# Bikota.net
KiCad netlist of a schematic drawn in EAGLE
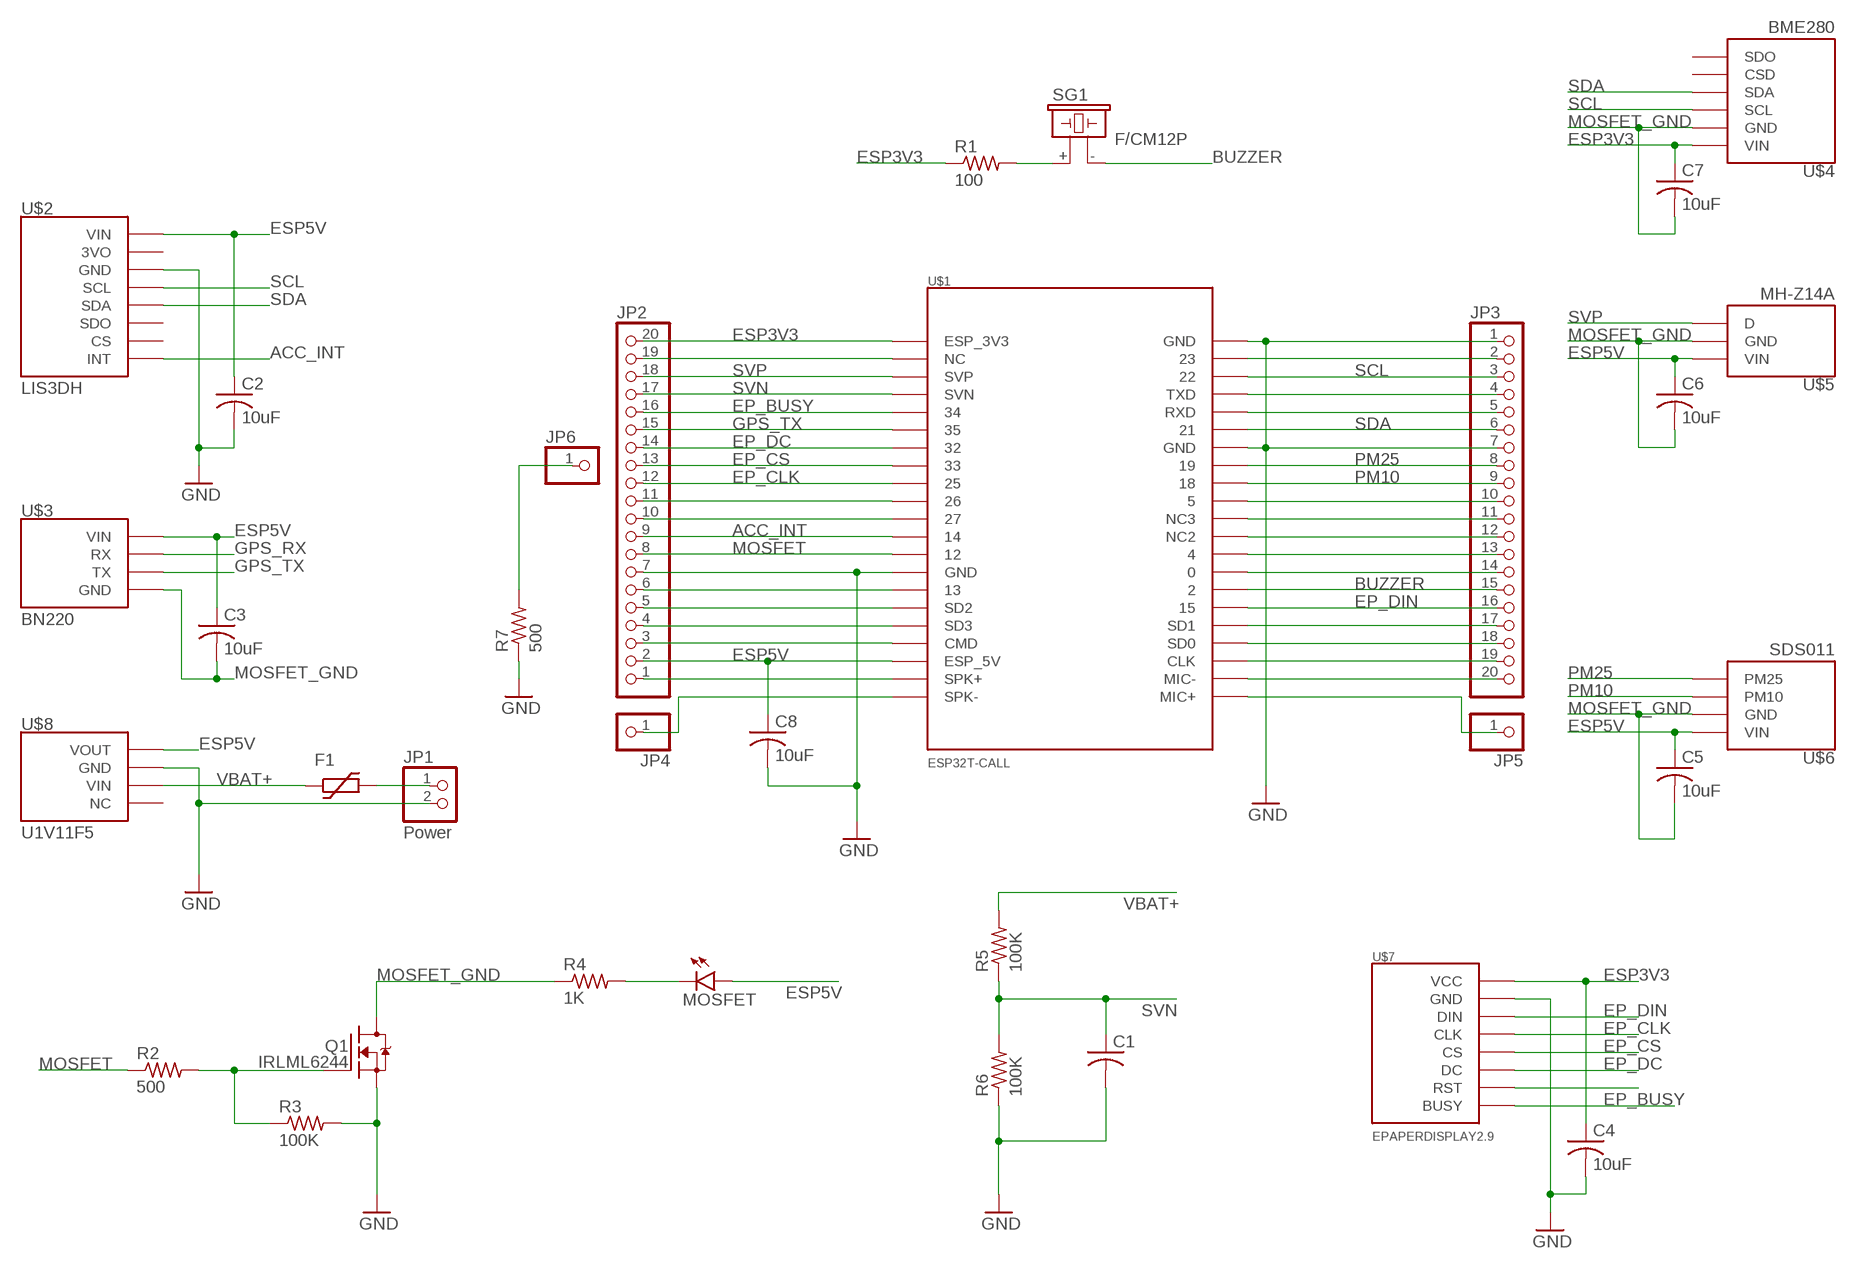
[diagram p0: schematic, sheet 1]

(export (version "E")
  (design (tool "Eeschema 10.0.6"))
  (components
    (comp (ref "C1")
      (value "C-USC0805")
      (footprint "eagle-import:C0805")
      (libsource (lib "eagle-import") (part "C-USC0805"))
    )
    (comp (ref "C2")
      (value "10uF")
      (footprint "eagle-import:C0805")
      (libsource (lib "eagle-import") (part "C-USC0805"))
    )
    (comp (ref "C3")
      (value "10uF")
      (footprint "eagle-import:C0805")
      (libsource (lib "eagle-import") (part "C-USC0805"))
    )
    (comp (ref "C4")
      (value "10uF")
      (footprint "eagle-import:C0805")
      (libsource (lib "eagle-import") (part "C-USC0805"))
    )
    (comp (ref "C5")
      (value "10uF")
      (footprint "eagle-import:C0805")
      (libsource (lib "eagle-import") (part "C-USC0805"))
    )
    (comp (ref "C6")
      (value "10uF")
      (footprint "eagle-import:C0805")
      (libsource (lib "eagle-import") (part "C-USC0805"))
    )
    (comp (ref "C7")
      (value "10uF")
      (footprint "eagle-import:C0805")
      (libsource (lib "eagle-import") (part "C-USC0805"))
    )
    (comp (ref "C8")
      (value "10uF")
      (footprint "eagle-import:C0805")
      (libsource (lib "eagle-import") (part "C-USC0805"))
    )
    (comp (ref "F1")
      (value "1206L")
      (footprint "eagle-import:1206L")
      (libsource (lib "eagle-import") (part "1206L"))
    )
    (comp (ref "JP1")
      (value "Power")
      (footprint "eagle-import:1X02")
      (libsource (lib "eagle-import") (part "PINHD-1X2"))
    )
    (comp (ref "JP2")
      (value "PINHD-1X20")
      (footprint "eagle-import:1X20")
      (libsource (lib "eagle-import") (part "PINHD-1X20"))
    )
    (comp (ref "JP3")
      (value "PINHD-1X20")
      (footprint "eagle-import:1X20")
      (libsource (lib "eagle-import") (part "PINHD-1X20"))
    )
    (comp (ref "JP4")
      (value "PINHD-1X1")
      (footprint "eagle-import:1X01")
      (libsource (lib "eagle-import") (part "PINHD-1X1"))
    )
    (comp (ref "JP5")
      (value "PINHD-1X1")
      (footprint "eagle-import:1X01")
      (libsource (lib "eagle-import") (part "PINHD-1X1"))
    )
    (comp (ref "JP6")
      (value "PINHD-1X1")
      (footprint "eagle-import:1X01")
      (libsource (lib "eagle-import") (part "PINHD-1X1"))
    )
    (comp (ref "MOSFET")
      (value "LEDCHIPLED_0805")
      (footprint "eagle-import:CHIPLED_0805")
      (libsource (lib "eagle-import") (part "LEDCHIPLED_0805"))
    )
    (comp (ref "Q1")
      (value "IRLML6244")
      (footprint "eagle-import:SOT23")
      (fields (field (name "MF") "Internat. Rectifier") (field (name "MPN") "IRLML6244TRPbF"))
      (libsource (lib "eagle-import") (part "IRLML6244"))
    )
    (comp (ref "R1")
      (value "100")
      (footprint "eagle-import:R0805")
      (libsource (lib "eagle-import") (part "R-US_R0805"))
    )
    (comp (ref "R2")
      (value "500")
      (footprint "eagle-import:R0805")
      (libsource (lib "eagle-import") (part "R-US_R0805"))
    )
    (comp (ref "R3")
      (value "100K")
      (footprint "eagle-import:R0805")
      (libsource (lib "eagle-import") (part "R-US_R0805"))
    )
    (comp (ref "R4")
      (value "1K")
      (footprint "eagle-import:R0805")
      (libsource (lib "eagle-import") (part "R-US_R0805"))
    )
    (comp (ref "R5")
      (value "100K")
      (footprint "eagle-import:R0805")
      (libsource (lib "eagle-import") (part "R-US_R0805"))
    )
    (comp (ref "R6")
      (value "100K")
      (footprint "eagle-import:R0805")
      (libsource (lib "eagle-import") (part "R-US_R0805"))
    )
    (comp (ref "R7")
      (value "500")
      (footprint "eagle-import:R0805")
      (libsource (lib "eagle-import") (part "R-US_R0805"))
    )
    (comp (ref "SG1")
      (value "F/CM12P")
      (footprint "eagle-import:F_CM12P")
      (libsource (lib "eagle-import") (part "F/CM12P"))
    )
    (comp (ref "U$1")
      (value "ESP32T-CALL")
      (footprint "eagle-import:ESP32T-CALL")
      (libsource (lib "eagle-import") (part "ESP32T-CALL"))
    )
    (comp (ref "U$2")
      (value "LIS3DH")
      (footprint "eagle-import:LIS3DH")
      (libsource (lib "eagle-import") (part "LIS3DH"))
    )
    (comp (ref "U$3")
      (value "BN220")
      (footprint "eagle-import:BN220")
      (libsource (lib "eagle-import") (part "BN220"))
    )
    (comp (ref "U$4")
      (value "BME280")
      (footprint "eagle-import:BME280")
      (libsource (lib "eagle-import") (part "BME280"))
    )
    (comp (ref "U$5")
      (value "MH-Z14A")
      (footprint "eagle-import:MH-Z14A")
      (libsource (lib "eagle-import") (part "MH-Z14A"))
    )
    (comp (ref "U$6")
      (value "SDS011")
      (footprint "eagle-import:SDS011")
      (libsource (lib "eagle-import") (part "SDS011"))
    )
    (comp (ref "U$7")
      (value "EPAPERDISPLAY2.9")
      (footprint "eagle-import:EPAPERDISPLAY2.9")
      (libsource (lib "eagle-import") (part "EPAPERDISPLAY2.9"))
    )
    (comp (ref "U$8")
      (value "U1V11F5")
      (footprint "eagle-import:U1V11F5")
      (libsource (lib "eagle-import") (part "U1V11F5"))
    )
  )
  (nets
    (net (code "1") (name "/3VO") (class "Default")
      (node (ref "U$2") (pin "P$2") (pinfunction "3VO_P$2") (pintype "power_in"))
    )
    (net (code "2") (name "/ACC_INT") (class "Default")
      (node (ref "JP2") (pin "9") (pinfunction "9_9") (pintype "passive"))
      (node (ref "U$1") (pin "GPIO14") (pinfunction "14_GPIO14") (pintype "bidirectional"))
      (node (ref "U$2") (pin "P$8") (pinfunction "INT_P$8") (pintype "bidirectional"))
    )
    (net (code "3") (name "/BUZZER") (class "Default")
      (node (ref "JP3") (pin "15") (pinfunction "15_15") (pintype "passive"))
      (node (ref "SG1") (pin "-") (pinfunction "2_-") (pintype "passive"))
      (node (ref "U$1") (pin "GPIO2") (pinfunction "2_GPIO2") (pintype "bidirectional"))
    )
    (net (code "4") (name "/EP_BUSY") (class "Default")
      (node (ref "JP2") (pin "16") (pinfunction "16_16") (pintype "passive"))
      (node (ref "U$1") (pin "GPIO34") (pinfunction "34_GPIO34") (pintype "bidirectional"))
      (node (ref "U$7") (pin "P$8") (pinfunction "BUSY_P$8") (pintype "bidirectional"))
    )
    (net (code "5") (name "/EP_CLK") (class "Default")
      (node (ref "JP2") (pin "12") (pinfunction "12_12") (pintype "passive"))
      (node (ref "U$1") (pin "GPIO25") (pinfunction "25_GPIO25") (pintype "bidirectional"))
      (node (ref "U$7") (pin "P$4") (pinfunction "CLK_P$4") (pintype "bidirectional"))
    )
    (net (code "6") (name "/EP_CS") (class "Default")
      (node (ref "JP2") (pin "13") (pinfunction "13_13") (pintype "passive"))
      (node (ref "U$1") (pin "GPIO33") (pinfunction "33_GPIO33") (pintype "bidirectional"))
      (node (ref "U$7") (pin "P$5") (pinfunction "CS_P$5") (pintype "bidirectional"))
    )
    (net (code "7") (name "/EP_DC") (class "Default")
      (node (ref "JP2") (pin "14") (pinfunction "14_14") (pintype "passive"))
      (node (ref "U$1") (pin "GPIO32") (pinfunction "32_GPIO32") (pintype "bidirectional"))
      (node (ref "U$7") (pin "P$6") (pinfunction "DC_P$6") (pintype "bidirectional"))
    )
    (net (code "8") (name "/EP_DIN") (class "Default")
      (node (ref "JP3") (pin "16") (pinfunction "16_16") (pintype "passive"))
      (node (ref "U$1") (pin "GPIO15") (pinfunction "15_GPIO15") (pintype "bidirectional"))
      (node (ref "U$7") (pin "P$3") (pinfunction "DIN_P$3") (pintype "bidirectional"))
    )
    (net (code "9") (name "/ESP3V3") (class "Default")
      (node (ref "C4") (pin "1") (pinfunction "1_1") (pintype "passive"))
      (node (ref "C7") (pin "1") (pinfunction "1_1") (pintype "passive"))
      (node (ref "JP2") (pin "20") (pinfunction "20_20") (pintype "passive"))
      (node (ref "R1") (pin "1") (pinfunction "1_1") (pintype "passive"))
      (node (ref "U$1") (pin "ESP32_3V3") (pinfunction "ESP_3V3_ESP32_3V3") (pintype "power_in"))
      (node (ref "U$4") (pin "P$1") (pinfunction "VIN_P$1") (pintype "power_in"))
      (node (ref "U$7") (pin "P$1") (pinfunction "VCC_P$1") (pintype "power_in"))
    )
    (net (code "10") (name "/ESP5V") (class "Default")
      (node (ref "C2") (pin "1") (pinfunction "1_1") (pintype "passive"))
      (node (ref "C3") (pin "1") (pinfunction "1_1") (pintype "passive"))
      (node (ref "C5") (pin "1") (pinfunction "1_1") (pintype "passive"))
      (node (ref "C6") (pin "1") (pinfunction "1_1") (pintype "passive"))
      (node (ref "C8") (pin "1") (pinfunction "1_1") (pintype "passive"))
      (node (ref "JP2") (pin "2") (pinfunction "2_2") (pintype "passive"))
      (node (ref "MOSFET") (pin "A") (pinfunction "A_A") (pintype "passive"))
      (node (ref "U$1") (pin "ESP32_5V") (pinfunction "ESP_5V_ESP32_5V") (pintype "power_in"))
      (node (ref "U$2") (pin "P$1") (pinfunction "VIN_P$1") (pintype "power_in"))
      (node (ref "U$3") (pin "P$1") (pinfunction "VIN_P$1") (pintype "power_in"))
      (node (ref "U$5") (pin "P$1") (pinfunction "VIN_P$1") (pintype "power_in"))
      (node (ref "U$6") (pin "P$1") (pinfunction "VIN_P$1") (pintype "power_in"))
      (node (ref "U$8") (pin "P$1") (pinfunction "VOUT_P$1") (pintype "power_in"))
    )
    (net (code "11") (name "/GPS_RX") (class "Default")
      (node (ref "U$3") (pin "P$2") (pinfunction "RX_P$2") (pintype "bidirectional"))
    )
    (net (code "12") (name "/GPS_TX") (class "Default")
      (node (ref "JP2") (pin "15") (pinfunction "15_15") (pintype "passive"))
      (node (ref "U$1") (pin "GPIO35") (pinfunction "35_GPIO35") (pintype "bidirectional"))
      (node (ref "U$3") (pin "P$3") (pinfunction "TX_P$3") (pintype "bidirectional"))
    )
    (net (code "13") (name "/MOSFET") (class "Default")
      (node (ref "JP2") (pin "8") (pinfunction "8_8") (pintype "passive"))
      (node (ref "R2") (pin "1") (pinfunction "1_1") (pintype "passive"))
      (node (ref "U$1") (pin "GPIO12") (pinfunction "12_GPIO12") (pintype "bidirectional"))
    )
    (net (code "14") (name "/MOSFET_GND") (class "Default")
      (node (ref "C3") (pin "2") (pinfunction "2_2") (pintype "passive"))
      (node (ref "C5") (pin "2") (pinfunction "2_2") (pintype "passive"))
      (node (ref "C6") (pin "2") (pinfunction "2_2") (pintype "passive"))
      (node (ref "C7") (pin "2") (pinfunction "2_2") (pintype "passive"))
      (node (ref "Q1") (pin "3") (pinfunction "D_3") (pintype "passive"))
      (node (ref "R4") (pin "1") (pinfunction "1_1") (pintype "passive"))
      (node (ref "U$3") (pin "P$4") (pinfunction "GND_P$4") (pintype "power_in"))
      (node (ref "U$4") (pin "P$2") (pinfunction "GND_P$2") (pintype "power_in"))
      (node (ref "U$5") (pin "P$2") (pinfunction "GND_P$2") (pintype "power_in"))
      (node (ref "U$6") (pin "P$2") (pinfunction "GND_P$2") (pintype "power_in"))
    )
    (net (code "15") (name "/PM10") (class "Default")
      (node (ref "JP3") (pin "9") (pinfunction "9_9") (pintype "passive"))
      (node (ref "U$1") (pin "GPIO18") (pinfunction "18_GPIO18") (pintype "bidirectional"))
      (node (ref "U$6") (pin "P$3") (pinfunction "PM10_P$3") (pintype "bidirectional"))
    )
    (net (code "16") (name "/PM25") (class "Default")
      (node (ref "JP3") (pin "8") (pinfunction "8_8") (pintype "passive"))
      (node (ref "U$1") (pin "GPIO19") (pinfunction "19_GPIO19") (pintype "bidirectional"))
      (node (ref "U$6") (pin "P$4") (pinfunction "PM25_P$4") (pintype "bidirectional"))
    )
    (net (code "17") (name "/SCL") (class "Default")
      (node (ref "JP3") (pin "3") (pinfunction "3_3") (pintype "passive"))
      (node (ref "U$1") (pin "GPIO22") (pinfunction "22_GPIO22") (pintype "bidirectional"))
      (node (ref "U$2") (pin "P$4") (pinfunction "SCL_P$4") (pintype "bidirectional"))
      (node (ref "U$4") (pin "P$3") (pinfunction "SCL_P$3") (pintype "bidirectional"))
    )
    (net (code "18") (name "/SDA") (class "Default")
      (node (ref "JP3") (pin "6") (pinfunction "6_6") (pintype "passive"))
      (node (ref "U$1") (pin "GPIO21") (pinfunction "21_GPIO21") (pintype "bidirectional"))
      (node (ref "U$2") (pin "P$5") (pinfunction "SDA_P$5") (pintype "bidirectional"))
      (node (ref "U$4") (pin "P$4") (pinfunction "SDA_P$4") (pintype "bidirectional"))
    )
    (net (code "19") (name "/SVN") (class "Default")
      (node (ref "C1") (pin "1") (pinfunction "1_1") (pintype "passive"))
      (node (ref "JP2") (pin "17") (pinfunction "17_17") (pintype "passive"))
      (node (ref "R5") (pin "1") (pinfunction "1_1") (pintype "passive"))
      (node (ref "R6") (pin "2") (pinfunction "2_2") (pintype "passive"))
      (node (ref "U$1") (pin "SVN") (pinfunction "SVN_SVN") (pintype "bidirectional"))
    )
    (net (code "20") (name "/SVP") (class "Default")
      (node (ref "JP2") (pin "18") (pinfunction "18_18") (pintype "passive"))
      (node (ref "U$1") (pin "SVP") (pinfunction "SVP_SVP") (pintype "bidirectional"))
      (node (ref "U$5") (pin "P$3") (pinfunction "D_P$3") (pintype "bidirectional"))
    )
    (net (code "21") (name "/VBAT+") (class "Default")
      (node (ref "F1") (pin "P$1") (pinfunction "1_P$1") (pintype "passive"))
      (node (ref "R5") (pin "2") (pinfunction "2_2") (pintype "passive"))
      (node (ref "U$8") (pin "P$3") (pinfunction "VIN_P$3") (pintype "power_in"))
    )
    (net (code "22") (name "GND") (class "Default")
      (node (ref "C1") (pin "2") (pinfunction "2_2") (pintype "passive"))
      (node (ref "C2") (pin "2") (pinfunction "2_2") (pintype "passive"))
      (node (ref "C4") (pin "2") (pinfunction "2_2") (pintype "passive"))
      (node (ref "C8") (pin "2") (pinfunction "2_2") (pintype "passive"))
      (node (ref "JP1") (pin "2") (pinfunction "2_2") (pintype "passive"))
      (node (ref "JP2") (pin "7") (pinfunction "7_7") (pintype "passive"))
      (node (ref "JP3") (pin "1") (pinfunction "1_1") (pintype "passive"))
      (node (ref "JP3") (pin "7") (pinfunction "7_7") (pintype "passive"))
      (node (ref "Q1") (pin "2") (pinfunction "S_2") (pintype "passive"))
      (node (ref "R3") (pin "2") (pinfunction "2_2") (pintype "passive"))
      (node (ref "R6") (pin "1") (pinfunction "1_1") (pintype "passive"))
      (node (ref "R7") (pin "1") (pinfunction "1_1") (pintype "passive"))
      (node (ref "U$1") (pin "GND") (pinfunction "GND_GND") (pintype "power_in"))
      (node (ref "U$1") (pin "GND2") (pinfunction "GND_GND2") (pintype "power_in"))
      (node (ref "U$1") (pin "GND3") (pinfunction "GND_GND3") (pintype "power_in"))
      (node (ref "U$2") (pin "P$3") (pinfunction "GND_P$3") (pintype "power_in"))
      (node (ref "U$7") (pin "P$2") (pinfunction "GND_P$2") (pintype "power_in"))
      (node (ref "U$8") (pin "P$2") (pinfunction "GND_P$2") (pintype "power_in"))
    )
    (net (code "23") (name "Net-(F1-2)") (class "Default")
      (node (ref "F1") (pin "P$2") (pinfunction "2_P$2") (pintype "passive"))
      (node (ref "JP1") (pin "1") (pinfunction "1_1") (pintype "passive"))
    )
    (net (code "24") (name "Net-(JP2-Pad1)") (class "Default")
      (node (ref "JP2") (pin "1") (pinfunction "1_1") (pintype "passive"))
      (node (ref "U$1") (pin "SPK+") (pinfunction "SPK+_SPK+") (pintype "bidirectional"))
    )
    (net (code "25") (name "Net-(JP2-Pad3)") (class "Default")
      (node (ref "JP2") (pin "3") (pinfunction "3_3") (pintype "passive"))
      (node (ref "U$1") (pin "CMD") (pinfunction "CMD_CMD") (pintype "bidirectional"))
    )
    (net (code "26") (name "Net-(JP2-Pad4)") (class "Default")
      (node (ref "JP2") (pin "4") (pinfunction "4_4") (pintype "passive"))
      (node (ref "U$1") (pin "SD3") (pinfunction "SD3_SD3") (pintype "bidirectional"))
    )
    (net (code "27") (name "Net-(JP2-Pad5)") (class "Default")
      (node (ref "JP2") (pin "5") (pinfunction "5_5") (pintype "passive"))
      (node (ref "U$1") (pin "SD2") (pinfunction "SD2_SD2") (pintype "bidirectional"))
    )
    (net (code "28") (name "Net-(JP3-Pad4)") (class "Default")
      (node (ref "JP3") (pin "4") (pinfunction "4_4") (pintype "passive"))
      (node (ref "U$1") (pin "TXD") (pinfunction "TXD_TXD") (pintype "bidirectional"))
    )
    (net (code "29") (name "Net-(JP3-Pad5)") (class "Default")
      (node (ref "JP3") (pin "5") (pinfunction "5_5") (pintype "passive"))
      (node (ref "U$1") (pin "RXD") (pinfunction "RXD_RXD") (pintype "bidirectional"))
    )
    (net (code "30") (name "Net-(JP3-Pad11)") (class "Default")
      (node (ref "JP3") (pin "11") (pinfunction "11_11") (pintype "passive"))
      (node (ref "U$1") (pin "NC3") (pinfunction "NC3_NC3") (pintype "bidirectional"))
    )
    (net (code "31") (name "Net-(JP3-Pad12)") (class "Default")
      (node (ref "JP3") (pin "12") (pinfunction "12_12") (pintype "passive"))
      (node (ref "U$1") (pin "NC2") (pinfunction "NC2_NC2") (pintype "bidirectional"))
    )
    (net (code "32") (name "Net-(JP3-Pad17)") (class "Default")
      (node (ref "JP3") (pin "17") (pinfunction "17_17") (pintype "passive"))
      (node (ref "U$1") (pin "SD1") (pinfunction "SD1_SD1") (pintype "bidirectional"))
    )
    (net (code "33") (name "Net-(JP3-Pad18)") (class "Default")
      (node (ref "JP3") (pin "18") (pinfunction "18_18") (pintype "passive"))
      (node (ref "U$1") (pin "SD0") (pinfunction "SD0_SD0") (pintype "bidirectional"))
    )
    (net (code "34") (name "Net-(JP3-Pad19)") (class "Default")
      (node (ref "JP3") (pin "19") (pinfunction "19_19") (pintype "passive"))
      (node (ref "U$1") (pin "CLK") (pinfunction "CLK_CLK") (pintype "bidirectional"))
    )
    (net (code "35") (name "Net-(JP3-Pad20)") (class "Default")
      (node (ref "JP3") (pin "20") (pinfunction "20_20") (pintype "passive"))
      (node (ref "U$1") (pin "MIC-") (pinfunction "MIC-_MIC-") (pintype "bidirectional"))
    )
    (net (code "36") (name "Net-(JP4-Pad1)") (class "Default")
      (node (ref "JP4") (pin "1") (pinfunction "1_1") (pintype "passive"))
      (node (ref "U$1") (pin "SPK-") (pinfunction "SPK-_SPK-") (pintype "bidirectional"))
    )
    (net (code "37") (name "Net-(JP5-Pad1)") (class "Default")
      (node (ref "JP5") (pin "1") (pinfunction "1_1") (pintype "passive"))
      (node (ref "U$1") (pin "MIC+") (pinfunction "MIC+_MIC+") (pintype "bidirectional"))
    )
    (net (code "38") (name "Net-(JP6-Pad1)") (class "Default")
      (node (ref "JP6") (pin "1") (pinfunction "1_1") (pintype "passive"))
      (node (ref "R7") (pin "2") (pinfunction "2_2") (pintype "passive"))
    )
    (net (code "39") (name "Net-(MOSFET-PadC)") (class "Default")
      (node (ref "MOSFET") (pin "C") (pinfunction "C_C") (pintype "passive"))
      (node (ref "R4") (pin "2") (pinfunction "2_2") (pintype "passive"))
    )
    (net (code "40") (name "Net-(Q1-G)") (class "Default")
      (node (ref "Q1") (pin "1") (pinfunction "G_1") (pintype "passive"))
      (node (ref "R2") (pin "2") (pinfunction "2_2") (pintype "passive"))
      (node (ref "R3") (pin "1") (pinfunction "1_1") (pintype "passive"))
    )
    (net (code "41") (name "Net-(SG1-1)") (class "Default")
      (node (ref "R1") (pin "2") (pinfunction "2_2") (pintype "passive"))
      (node (ref "SG1") (pin "+") (pinfunction "1_+") (pintype "passive"))
    )
    (net (code "42") (name "Net-(U$1-0)") (class "Default")
      (node (ref "JP3") (pin "14") (pinfunction "14_14") (pintype "passive"))
      (node (ref "U$1") (pin "GPIO0") (pinfunction "0_GPIO0") (pintype "bidirectional"))
    )
    (net (code "43") (name "Net-(U$1-4)") (class "Default")
      (node (ref "JP3") (pin "13") (pinfunction "13_13") (pintype "passive"))
      (node (ref "U$1") (pin "GPIO4") (pinfunction "4_GPIO4") (pintype "bidirectional"))
    )
    (net (code "44") (name "Net-(U$1-5)") (class "Default")
      (node (ref "JP3") (pin "10") (pinfunction "10_10") (pintype "passive"))
      (node (ref "U$1") (pin "GPIO5") (pinfunction "5_GPIO5") (pintype "bidirectional"))
    )
    (net (code "45") (name "Net-(U$1-13)") (class "Default")
      (node (ref "JP2") (pin "6") (pinfunction "6_6") (pintype "passive"))
      (node (ref "U$1") (pin "GPIO13") (pinfunction "13_GPIO13") (pintype "bidirectional"))
    )
    (net (code "46") (name "Net-(U$1-23)") (class "Default")
      (node (ref "JP3") (pin "2") (pinfunction "2_2") (pintype "passive"))
      (node (ref "U$1") (pin "GPIO23") (pinfunction "23_GPIO23") (pintype "bidirectional"))
    )
    (net (code "47") (name "Net-(U$1-26)") (class "Default")
      (node (ref "JP2") (pin "11") (pinfunction "11_11") (pintype "passive"))
      (node (ref "U$1") (pin "GPIO26") (pinfunction "26_GPIO26") (pintype "bidirectional"))
    )
    (net (code "48") (name "Net-(U$1-27)") (class "Default")
      (node (ref "JP2") (pin "10") (pinfunction "10_10") (pintype "passive"))
      (node (ref "U$1") (pin "GPIO27") (pinfunction "27_GPIO27") (pintype "bidirectional"))
    )
    (net (code "49") (name "Net-(U$1-NC)") (class "Default")
      (node (ref "JP2") (pin "19") (pinfunction "19_19") (pintype "passive"))
      (node (ref "U$1") (pin "P$2") (pinfunction "NC_P$2") (pintype "bidirectional"))
    )
    (net (code "50") (name "unconnected-(U$2-CS-PadP$7)") (class "Default")
      (node (ref "U$2") (pin "P$7") (pinfunction "CS_P$7") (pintype "bidirectional"))
    )
    (net (code "51") (name "unconnected-(U$2-SDO-PadP$6)") (class "Default")
      (node (ref "U$2") (pin "P$6") (pinfunction "SDO_P$6") (pintype "bidirectional"))
    )
    (net (code "52") (name "unconnected-(U$4-CSD-PadP$5)") (class "Default")
      (node (ref "U$4") (pin "P$5") (pinfunction "CSD_P$5") (pintype "bidirectional"))
    )
    (net (code "53") (name "unconnected-(U$4-SDO-PadP$6)") (class "Default")
      (node (ref "U$4") (pin "P$6") (pinfunction "SDO_P$6") (pintype "bidirectional"))
    )
    (net (code "54") (name "unconnected-(U$7-RST-PadP$7)") (class "Default")
      (node (ref "U$7") (pin "P$7") (pinfunction "RST_P$7") (pintype "bidirectional"))
    )
    (net (code "55") (name "unconnected-(U$8-NC-PadP$4)") (class "Default")
      (node (ref "U$8") (pin "P$4") (pinfunction "NC_P$4") (pintype "no_connect"))
    )
  )
)
